# Cosmic_Pi_Analogue_V2_4_OHL_logo.net
KiCad netlist of a schematic drawn in EAGLE
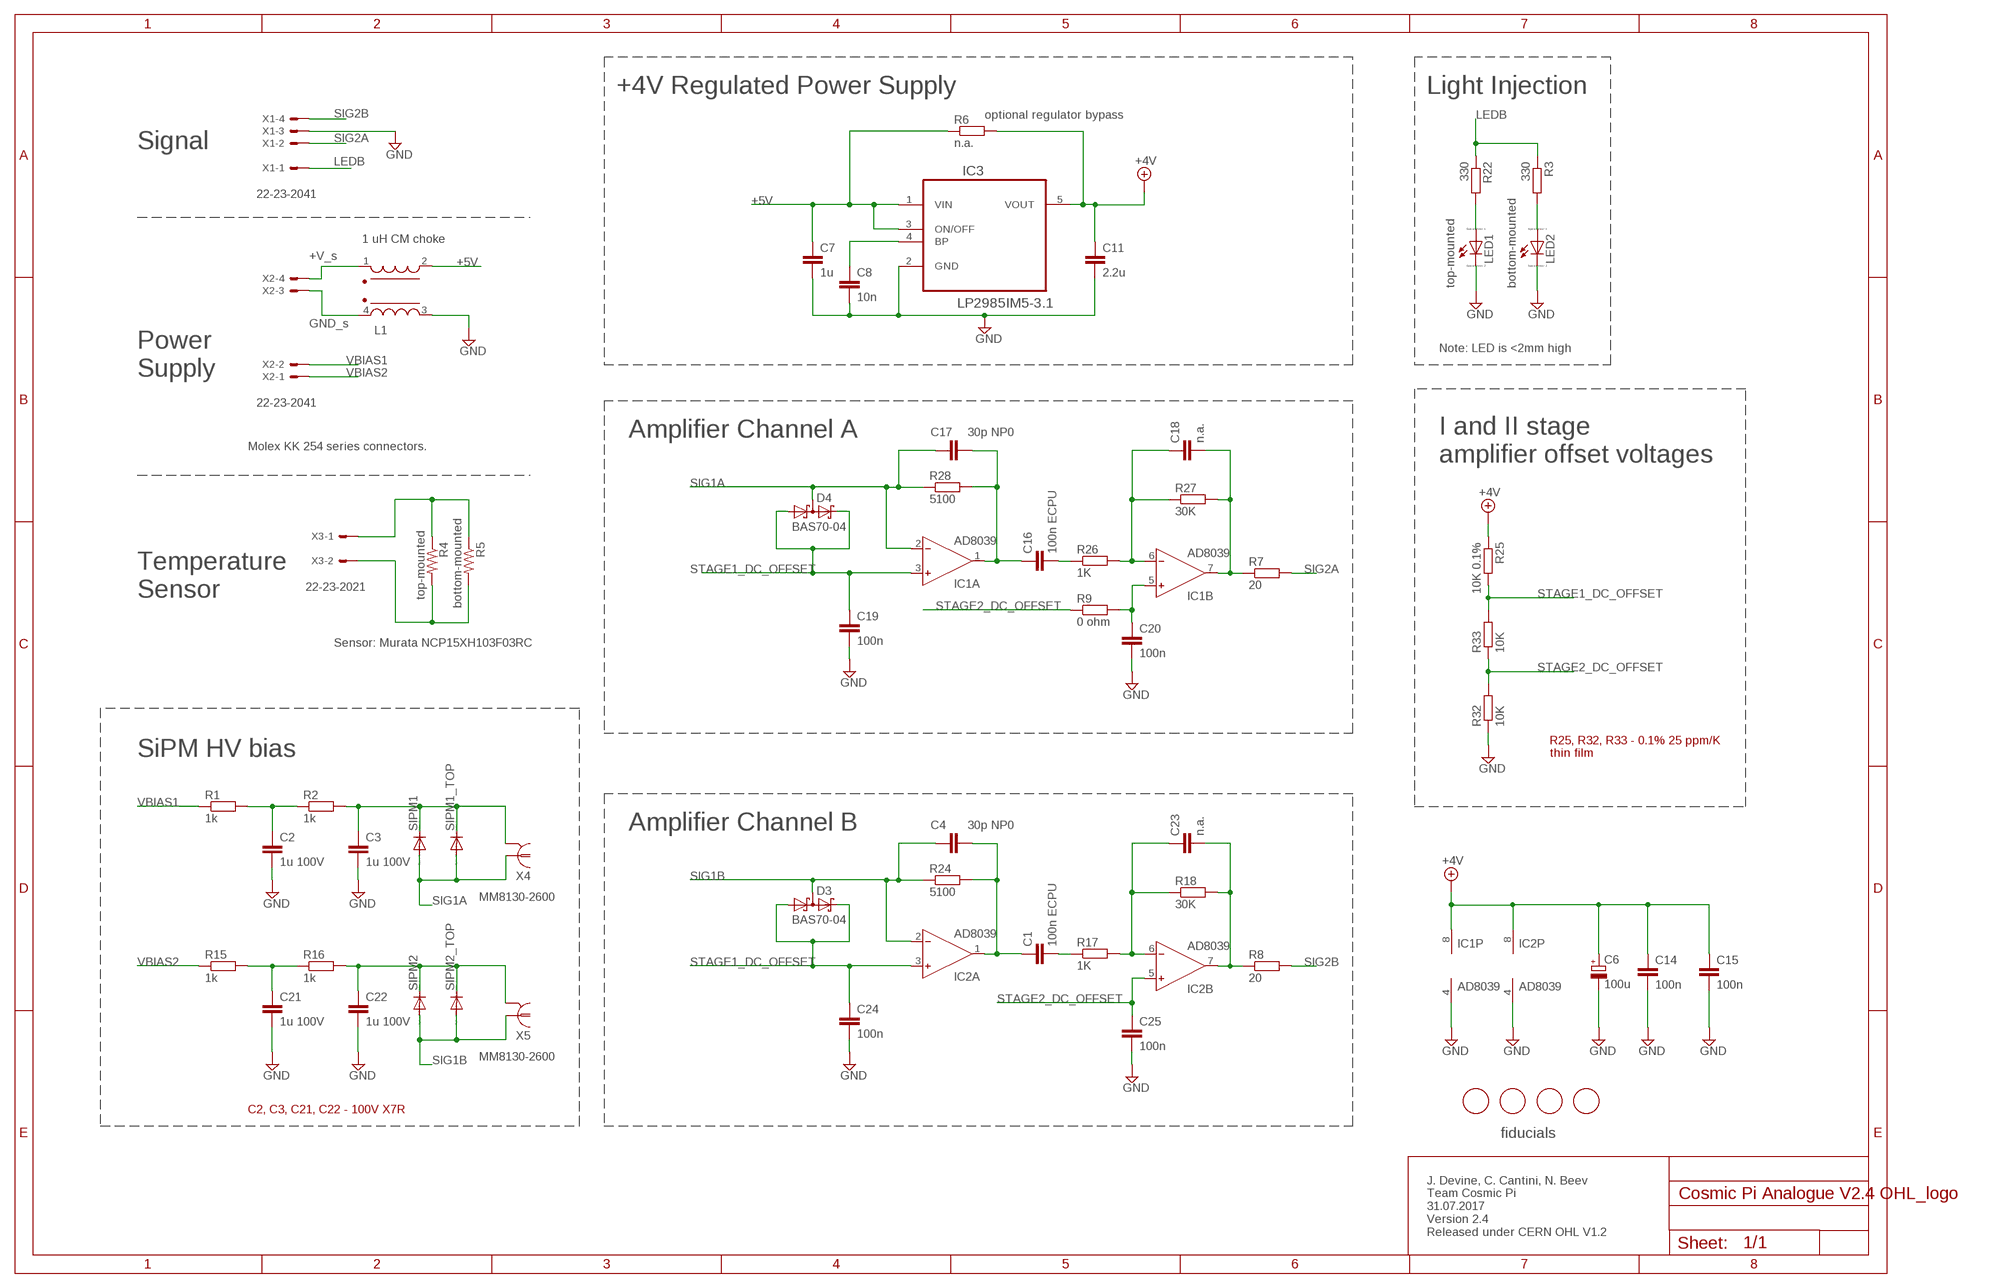
[diagram p0: schematic, sheet 1]

(export (version "E")
  (design (tool "Eeschema 10.0.6"))
  (components
    (comp (ref "C1")
      (value "100n ECPU")
      (footprint "eagle-import:C0805")
      (libsource (lib "eagle-import") (part "C-EUC0805"))
    )
    (comp (ref "C2")
      (value "1u 100V")
      (footprint "eagle-import:C1206")
      (libsource (lib "eagle-import") (part "C-EUC1206"))
    )
    (comp (ref "C3")
      (value "1u 100V")
      (footprint "eagle-import:C1206")
      (libsource (lib "eagle-import") (part "C-EUC1206"))
    )
    (comp (ref "C4")
      (value "30p NP0")
      (footprint "eagle-import:C0603")
      (libsource (lib "eagle-import") (part "C-EUC0603"))
    )
    (comp (ref "C6")
      (value "100u")
      (footprint "eagle-import:C_6032-28R")
      (libsource (lib "eagle-import") (part "CPOL-EUC/6032-28R"))
    )
    (comp (ref "C7")
      (value "1u")
      (footprint "eagle-import:C0603")
      (libsource (lib "eagle-import") (part "resistor_C-EUC0603"))
    )
    (comp (ref "C8")
      (value "10n")
      (footprint "eagle-import:C0603")
      (libsource (lib "eagle-import") (part "resistor_C-EUC0603"))
    )
    (comp (ref "C11")
      (value "2.2u")
      (footprint "eagle-import:C0603")
      (libsource (lib "eagle-import") (part "resistor_C-EUC0603"))
    )
    (comp (ref "C14")
      (value "100n")
      (footprint "eagle-import:C0603")
      (libsource (lib "eagle-import") (part "resistor_C-EUC0603"))
    )
    (comp (ref "C15")
      (value "100n")
      (footprint "eagle-import:C0603")
      (libsource (lib "eagle-import") (part "resistor_C-EUC0603"))
    )
    (comp (ref "C16")
      (value "100n ECPU")
      (footprint "eagle-import:C0805")
      (libsource (lib "eagle-import") (part "C-EUC0805"))
    )
    (comp (ref "C17")
      (value "30p NP0")
      (footprint "eagle-import:C0603")
      (libsource (lib "eagle-import") (part "C-EUC0603"))
    )
    (comp (ref "C18")
      (value "n.a.")
      (footprint "eagle-import:C0603")
      (libsource (lib "eagle-import") (part "C-EUC0603"))
    )
    (comp (ref "C19")
      (value "100n")
      (footprint "eagle-import:C0603")
      (libsource (lib "eagle-import") (part "resistor_C-EUC0603"))
    )
    (comp (ref "C20")
      (value "100n")
      (footprint "eagle-import:C0603")
      (libsource (lib "eagle-import") (part "resistor_C-EUC0603"))
    )
    (comp (ref "C21")
      (value "1u 100V")
      (footprint "eagle-import:C1206")
      (libsource (lib "eagle-import") (part "C-EUC1206"))
    )
    (comp (ref "C22")
      (value "1u 100V")
      (footprint "eagle-import:C1206")
      (libsource (lib "eagle-import") (part "C-EUC1206"))
    )
    (comp (ref "C23")
      (value "n.a.")
      (footprint "eagle-import:C0603")
      (libsource (lib "eagle-import") (part "C-EUC0603"))
    )
    (comp (ref "C24")
      (value "100n")
      (footprint "eagle-import:C0603")
      (libsource (lib "eagle-import") (part "resistor_C-EUC0603"))
    )
    (comp (ref "C25")
      (value "100n")
      (footprint "eagle-import:C0603")
      (libsource (lib "eagle-import") (part "resistor_C-EUC0603"))
    )
    (comp (ref "D3")
      (value "BAS70-04")
      (footprint "eagle-import:SOT23")
      (libsource (lib "eagle-import") (part "BAS70-04"))
    )
    (comp (ref "D4")
      (value "BAS70-04")
      (footprint "eagle-import:SOT23")
      (libsource (lib "eagle-import") (part "BAS70-04"))
    )
    (comp (ref "IC1")
      (value "AD8039")
      (footprint "eagle-import:SO8")
      (fields (field (name "MF") "ALTERA CORPORATION") (field (name "MPN") "AD8033ARZ"))
      (libsource (lib "eagle-import") (part "AD8033R"))
    )
    (comp (ref "IC2")
      (value "AD8039")
      (footprint "eagle-import:SO8")
      (fields (field (name "MF") "ALTERA CORPORATION") (field (name "MPN") "AD8033ARZ"))
      (libsource (lib "eagle-import") (part "AD8033R"))
    )
    (comp (ref "IC3")
      (value "LP2985IM5-3.1")
      (footprint "eagle-import:SOT95P284X120-5N")
      (libsource (lib "eagle-import") (part "LP2985IM5-3.1"))
    )
    (comp (ref "L1")
      (value "1 uH CM choke")
      (footprint "eagle-import:WE-CNSW_1812")
      (libsource (lib "eagle-import") (part "WE-CNSW_1812_744235601"))
    )
    (comp (ref "LED1")
      (value "top-mounted")
      (footprint "eagle-import:LED_SML0603")
      (libsource (lib "eagle-import") (part "LED_ESML0603"))
    )
    (comp (ref "LED2")
      (value "bottom-mounted")
      (footprint "eagle-import:LED_SML0603")
      (libsource (lib "eagle-import") (part "LED_ESML0603"))
    )
    (comp (ref "R1")
      (value "1k")
      (footprint "eagle-import:R1206")
      (libsource (lib "eagle-import") (part "R-EU_R1206"))
    )
    (comp (ref "R2")
      (value "1k")
      (footprint "eagle-import:R1206")
      (libsource (lib "eagle-import") (part "R-EU_R1206"))
    )
    (comp (ref "R3")
      (value "330")
      (footprint "eagle-import:R0603")
      (libsource (lib "eagle-import") (part "resistor_R-EU_R0603"))
    )
    (comp (ref "R4")
      (value "top-mounted")
      (footprint "eagle-import:R0402")
      (libsource (lib "eagle-import") (part "R-US_R0402"))
    )
    (comp (ref "R5")
      (value "bottom-mounted")
      (footprint "eagle-import:R0402")
      (libsource (lib "eagle-import") (part "R-US_R0402"))
    )
    (comp (ref "R6")
      (value "n.a.")
      (footprint "eagle-import:R0603")
      (libsource (lib "eagle-import") (part "R-EU_R0603"))
    )
    (comp (ref "R7")
      (value "20")
      (footprint "eagle-import:R0603")
      (libsource (lib "eagle-import") (part "R-EU_R0603"))
    )
    (comp (ref "R8")
      (value "20")
      (footprint "eagle-import:R0603")
      (libsource (lib "eagle-import") (part "R-EU_R0603"))
    )
    (comp (ref "R9")
      (value "0 ohm")
      (footprint "eagle-import:R1206")
      (libsource (lib "eagle-import") (part "R-EU_R1206"))
    )
    (comp (ref "R15")
      (value "1k")
      (footprint "eagle-import:R1206")
      (libsource (lib "eagle-import") (part "R-EU_R1206"))
    )
    (comp (ref "R16")
      (value "1k")
      (footprint "eagle-import:R1206")
      (libsource (lib "eagle-import") (part "R-EU_R1206"))
    )
    (comp (ref "R17")
      (value "1K")
      (footprint "eagle-import:R0603")
      (libsource (lib "eagle-import") (part "R-EU_R0603"))
    )
    (comp (ref "R18")
      (value "30K")
      (footprint "eagle-import:R0603")
      (libsource (lib "eagle-import") (part "R-EU_R0603"))
    )
    (comp (ref "R22")
      (value "330")
      (footprint "eagle-import:R0603")
      (libsource (lib "eagle-import") (part "resistor_R-EU_R0603"))
    )
    (comp (ref "R24")
      (value "5100")
      (footprint "eagle-import:R0603")
      (libsource (lib "eagle-import") (part "R-EU_R0603"))
    )
    (comp (ref "R25")
      (value "10K 0.1%")
      (footprint "eagle-import:R0805")
      (libsource (lib "eagle-import") (part "R-EU_R0805"))
    )
    (comp (ref "R26")
      (value "1K")
      (footprint "eagle-import:R0603")
      (libsource (lib "eagle-import") (part "R-EU_R0603"))
    )
    (comp (ref "R27")
      (value "30K")
      (footprint "eagle-import:R0603")
      (libsource (lib "eagle-import") (part "R-EU_R0603"))
    )
    (comp (ref "R28")
      (value "5100")
      (footprint "eagle-import:R0603")
      (libsource (lib "eagle-import") (part "R-EU_R0603"))
    )
    (comp (ref "R32")
      (value "10K")
      (footprint "eagle-import:R0805")
      (libsource (lib "eagle-import") (part "R-EU_R0805"))
    )
    (comp (ref "R33")
      (value "10K")
      (footprint "eagle-import:R0805")
      (libsource (lib "eagle-import") (part "R-EU_R0805"))
    )
    (comp (ref "SIPM1")
      (value "DIODE-ADVANSID")
      (footprint "eagle-import:ASD-NUV3S-P")
      (libsource (lib "eagle-import") (part "DIODE-ADVANSID"))
    )
    (comp (ref "SIPM1_TOP")
      (value "DIODE-ADVANSID")
      (footprint "eagle-import:ASD-NUV3S-P")
      (libsource (lib "eagle-import") (part "DIODE-ADVANSID"))
    )
    (comp (ref "SIPM2")
      (value "DIODE-ADVANSID")
      (footprint "eagle-import:ASD-NUV3S-P")
      (libsource (lib "eagle-import") (part "DIODE-ADVANSID"))
    )
    (comp (ref "SIPM2_TOP")
      (value "DIODE-ADVANSID")
      (footprint "eagle-import:ASD-NUV3S-P")
      (libsource (lib "eagle-import") (part "DIODE-ADVANSID"))
    )
    (comp (ref "U$2")
      (value "FIDUCIAL")
      (footprint "eagle-import:FIDUCIAL_1MM")
      (libsource (lib "eagle-import") (part "FIDUCIAL"))
    )
    (comp (ref "U$3")
      (value "FIDUCIAL")
      (footprint "eagle-import:FIDUCIAL_1MM")
      (libsource (lib "eagle-import") (part "FIDUCIAL"))
    )
    (comp (ref "U$4")
      (value "FIDUCIAL")
      (footprint "eagle-import:FIDUCIAL_1MM")
      (libsource (lib "eagle-import") (part "FIDUCIAL"))
    )
    (comp (ref "U$5")
      (value "FIDUCIAL")
      (footprint "eagle-import:FIDUCIAL_1MM")
      (libsource (lib "eagle-import") (part "FIDUCIAL"))
    )
    (comp (ref "X1")
      (value "22-23-2041")
      (footprint "eagle-import:22-23-2041")
      (fields (field (name "MF") "MOLEX"))
      (libsource (lib "eagle-import") (part "22-23-2041"))
    )
    (comp (ref "X2")
      (value "22-23-2041")
      (footprint "eagle-import:22-23-2041")
      (fields (field (name "MF") "MOLEX"))
      (libsource (lib "eagle-import") (part "22-23-2041"))
    )
    (comp (ref "X3")
      (value "22-23-2021")
      (footprint "eagle-import:22-23-2021")
      (fields (field (name "MF") "MOLEX"))
      (libsource (lib "eagle-import") (part "22-23-2021"))
    )
    (comp (ref "X4")
      (value "MM8130-2600")
      (footprint "eagle-import:MM8130-2600")
      (libsource (lib "eagle-import") (part "MM8130-2600"))
    )
    (comp (ref "X5")
      (value "MM8130-2600")
      (footprint "eagle-import:MM8130-2600")
      (libsource (lib "eagle-import") (part "MM8130-2600"))
    )
  )
  (nets
    (net (code "1") (name "+4V") (class "Default")
      (node (ref "C11") (pin "1") (pinfunction "1_1") (pintype "passive"))
      (node (ref "C14") (pin "1") (pinfunction "1_1") (pintype "passive"))
      (node (ref "C15") (pin "1") (pinfunction "1_1") (pintype "passive"))
      (node (ref "C6") (pin "+") (pinfunction "+_+") (pintype "passive"))
      (node (ref "IC1") (pin "8") (pinfunction "V+_8") (pintype "power_in"))
      (node (ref "IC2") (pin "8") (pinfunction "V+_8") (pintype "power_in"))
      (node (ref "IC3") (pin "5") (pinfunction "VOUT_5") (pintype "output"))
      (node (ref "R25") (pin "1") (pinfunction "1_1") (pintype "passive"))
      (node (ref "R6") (pin "2") (pinfunction "2_2") (pintype "passive"))
    )
    (net (code "2") (name "/+5V") (class "Default")
      (node (ref "C7") (pin "1") (pinfunction "1_1") (pintype "passive"))
      (node (ref "IC3") (pin "1") (pinfunction "VIN_1") (pintype "power_in"))
      (node (ref "IC3") (pin "3") (pinfunction "ON/OFF_3") (pintype "input"))
      (node (ref "L1") (pin "2") (pinfunction "3_2") (pintype "passive"))
      (node (ref "R6") (pin "1") (pinfunction "1_1") (pintype "passive"))
    )
    (net (code "3") (name "/LEDB") (class "Default")
      (node (ref "R22") (pin "1") (pinfunction "1_1") (pintype "passive"))
      (node (ref "R3") (pin "1") (pinfunction "1_1") (pintype "passive"))
      (node (ref "X1") (pin "1") (pinfunction "S_1") (pintype "passive"))
    )
    (net (code "4") (name "/SIG1A") (class "Default")
      (node (ref "C17") (pin "1") (pinfunction "1_1") (pintype "passive"))
      (node (ref "D4") (pin "3") (pinfunction "C1A2_3") (pintype "passive"))
      (node (ref "IC1") (pin "2") (pinfunction "IN-_2") (pintype "input"))
      (node (ref "R28") (pin "1") (pinfunction "1_1") (pintype "passive"))
      (node (ref "SIPM1") (pin "P$2") (pinfunction "A_P$2") (pintype "passive"))
      (node (ref "SIPM1_TOP") (pin "P$2") (pinfunction "A_P$2") (pintype "passive"))
      (node (ref "X4") (pin "P$1") (pinfunction "1_P$1") (pintype "passive"))
      (node (ref "X4") (pin "P$2") (pinfunction "1_P$2") (pintype "passive"))
    )
    (net (code "5") (name "/SIG1B") (class "Default")
      (node (ref "C4") (pin "1") (pinfunction "1_1") (pintype "passive"))
      (node (ref "D3") (pin "3") (pinfunction "C1A2_3") (pintype "passive"))
      (node (ref "IC2") (pin "2") (pinfunction "IN-_2") (pintype "input"))
      (node (ref "R24") (pin "1") (pinfunction "1_1") (pintype "passive"))
      (node (ref "SIPM2") (pin "P$2") (pinfunction "A_P$2") (pintype "passive"))
      (node (ref "SIPM2_TOP") (pin "P$2") (pinfunction "A_P$2") (pintype "passive"))
      (node (ref "X5") (pin "P$1") (pinfunction "1_P$1") (pintype "passive"))
      (node (ref "X5") (pin "P$2") (pinfunction "1_P$2") (pintype "passive"))
    )
    (net (code "6") (name "/SIG2A") (class "Default")
      (node (ref "R7") (pin "2") (pinfunction "2_2") (pintype "passive"))
      (node (ref "X1") (pin "2") (pinfunction "S_2") (pintype "passive"))
    )
    (net (code "7") (name "/SIG2B") (class "Default")
      (node (ref "R8") (pin "2") (pinfunction "2_2") (pintype "passive"))
      (node (ref "X1") (pin "4") (pinfunction "S_4") (pintype "passive"))
    )
    (net (code "8") (name "/STAGE1_DC_OFFSET") (class "Default")
      (node (ref "C19") (pin "1") (pinfunction "1_1") (pintype "passive"))
      (node (ref "C24") (pin "1") (pinfunction "1_1") (pintype "passive"))
      (node (ref "D3") (pin "1") (pinfunction "A1_1") (pintype "passive"))
      (node (ref "D3") (pin "2") (pinfunction "C2_2") (pintype "passive"))
      (node (ref "D4") (pin "1") (pinfunction "A1_1") (pintype "passive"))
      (node (ref "D4") (pin "2") (pinfunction "C2_2") (pintype "passive"))
      (node (ref "IC1") (pin "3") (pinfunction "IN+_3") (pintype "input"))
      (node (ref "IC2") (pin "3") (pinfunction "IN+_3") (pintype "input"))
      (node (ref "R25") (pin "2") (pinfunction "2_2") (pintype "passive"))
      (node (ref "R33") (pin "2") (pinfunction "2_2") (pintype "passive"))
    )
    (net (code "9") (name "/STAGE2_DC_OFFSET") (class "Default")
      (node (ref "C25") (pin "1") (pinfunction "1_1") (pintype "passive"))
      (node (ref "IC2") (pin "5") (pinfunction "IN+_5") (pintype "input"))
      (node (ref "R32") (pin "2") (pinfunction "2_2") (pintype "passive"))
      (node (ref "R33") (pin "1") (pinfunction "1_1") (pintype "passive"))
      (node (ref "R9") (pin "1") (pinfunction "1_1") (pintype "passive"))
    )
    (net (code "10") (name "/VBIAS1") (class "Default")
      (node (ref "R1") (pin "1") (pinfunction "1_1") (pintype "passive"))
      (node (ref "X2") (pin "2") (pinfunction "S_2") (pintype "passive"))
    )
    (net (code "11") (name "/VBIAS2") (class "Default")
      (node (ref "R15") (pin "1") (pinfunction "1_1") (pintype "passive"))
      (node (ref "X2") (pin "1") (pinfunction "S_1") (pintype "passive"))
    )
    (net (code "12") (name "GND") (class "Default")
      (node (ref "C11") (pin "2") (pinfunction "2_2") (pintype "passive"))
      (node (ref "C14") (pin "2") (pinfunction "2_2") (pintype "passive"))
      (node (ref "C15") (pin "2") (pinfunction "2_2") (pintype "passive"))
      (node (ref "C19") (pin "2") (pinfunction "2_2") (pintype "passive"))
      (node (ref "C2") (pin "2") (pinfunction "2_2") (pintype "passive"))
      (node (ref "C20") (pin "2") (pinfunction "2_2") (pintype "passive"))
      (node (ref "C21") (pin "2") (pinfunction "2_2") (pintype "passive"))
      (node (ref "C22") (pin "2") (pinfunction "2_2") (pintype "passive"))
      (node (ref "C24") (pin "2") (pinfunction "2_2") (pintype "passive"))
      (node (ref "C25") (pin "2") (pinfunction "2_2") (pintype "passive"))
      (node (ref "C3") (pin "2") (pinfunction "2_2") (pintype "passive"))
      (node (ref "C6") (pin "-") (pinfunction "-_-") (pintype "passive"))
      (node (ref "C7") (pin "2") (pinfunction "2_2") (pintype "passive"))
      (node (ref "C8") (pin "2") (pinfunction "2_2") (pintype "passive"))
      (node (ref "IC1") (pin "4") (pinfunction "V-_4") (pintype "power_in"))
      (node (ref "IC2") (pin "4") (pinfunction "V-_4") (pintype "power_in"))
      (node (ref "IC3") (pin "2") (pinfunction "GND_2") (pintype "passive"))
      (node (ref "L1") (pin "3") (pinfunction "2_3") (pintype "passive"))
      (node (ref "LED1") (pin "C") (pinfunction "C_C") (pintype "passive"))
      (node (ref "LED2") (pin "C") (pinfunction "C_C") (pintype "passive"))
      (node (ref "R32") (pin "1") (pinfunction "1_1") (pintype "passive"))
      (node (ref "X1") (pin "3") (pinfunction "S_3") (pintype "passive"))
    )
    (net (code "13") (name "Net-(C1-Pad2)") (class "Default")
      (node (ref "C1") (pin "2") (pinfunction "2_2") (pintype "passive"))
      (node (ref "R17") (pin "1") (pinfunction "1_1") (pintype "passive"))
    )
    (net (code "14") (name "Net-(C2-Pad1)") (class "Default")
      (node (ref "C2") (pin "1") (pinfunction "1_1") (pintype "passive"))
      (node (ref "R1") (pin "2") (pinfunction "2_2") (pintype "passive"))
      (node (ref "R2") (pin "1") (pinfunction "1_1") (pintype "passive"))
    )
    (net (code "15") (name "Net-(C16-Pad2)") (class "Default")
      (node (ref "C16") (pin "2") (pinfunction "2_2") (pintype "passive"))
      (node (ref "R26") (pin "1") (pinfunction "1_1") (pintype "passive"))
    )
    (net (code "16") (name "Net-(C21-Pad1)") (class "Default")
      (node (ref "C21") (pin "1") (pinfunction "1_1") (pintype "passive"))
      (node (ref "R15") (pin "2") (pinfunction "2_2") (pintype "passive"))
      (node (ref "R16") (pin "1") (pinfunction "1_1") (pintype "passive"))
    )
    (net (code "17") (name "Net-(IC1A-OUT)") (class "Default")
      (node (ref "C16") (pin "1") (pinfunction "1_1") (pintype "passive"))
      (node (ref "C17") (pin "2") (pinfunction "2_2") (pintype "passive"))
      (node (ref "IC1") (pin "1") (pinfunction "OUT_1") (pintype "output"))
      (node (ref "R28") (pin "2") (pinfunction "2_2") (pintype "passive"))
    )
    (net (code "18") (name "Net-(IC1B-IN+)") (class "Default")
      (node (ref "C20") (pin "1") (pinfunction "1_1") (pintype "passive"))
      (node (ref "IC1") (pin "5") (pinfunction "IN+_5") (pintype "input"))
      (node (ref "R9") (pin "2") (pinfunction "2_2") (pintype "passive"))
    )
    (net (code "19") (name "Net-(IC1B-IN-)") (class "Default")
      (node (ref "C18") (pin "1") (pinfunction "1_1") (pintype "passive"))
      (node (ref "IC1") (pin "6") (pinfunction "IN-_6") (pintype "input"))
      (node (ref "R26") (pin "2") (pinfunction "2_2") (pintype "passive"))
      (node (ref "R27") (pin "1") (pinfunction "1_1") (pintype "passive"))
    )
    (net (code "20") (name "Net-(IC1B-OUT)") (class "Default")
      (node (ref "C18") (pin "2") (pinfunction "2_2") (pintype "passive"))
      (node (ref "IC1") (pin "7") (pinfunction "OUT_7") (pintype "output"))
      (node (ref "R27") (pin "2") (pinfunction "2_2") (pintype "passive"))
      (node (ref "R7") (pin "1") (pinfunction "1_1") (pintype "passive"))
    )
    (net (code "21") (name "Net-(IC2A-OUT)") (class "Default")
      (node (ref "C1") (pin "1") (pinfunction "1_1") (pintype "passive"))
      (node (ref "C4") (pin "2") (pinfunction "2_2") (pintype "passive"))
      (node (ref "IC2") (pin "1") (pinfunction "OUT_1") (pintype "output"))
      (node (ref "R24") (pin "2") (pinfunction "2_2") (pintype "passive"))
    )
    (net (code "22") (name "Net-(IC2B-IN-)") (class "Default")
      (node (ref "C23") (pin "1") (pinfunction "1_1") (pintype "passive"))
      (node (ref "IC2") (pin "6") (pinfunction "IN-_6") (pintype "input"))
      (node (ref "R17") (pin "2") (pinfunction "2_2") (pintype "passive"))
      (node (ref "R18") (pin "1") (pinfunction "1_1") (pintype "passive"))
    )
    (net (code "23") (name "Net-(IC2B-OUT)") (class "Default")
      (node (ref "C23") (pin "2") (pinfunction "2_2") (pintype "passive"))
      (node (ref "IC2") (pin "7") (pinfunction "OUT_7") (pintype "output"))
      (node (ref "R18") (pin "2") (pinfunction "2_2") (pintype "passive"))
      (node (ref "R8") (pin "1") (pinfunction "1_1") (pintype "passive"))
    )
    (net (code "24") (name "Net-(IC3-BP)") (class "Default")
      (node (ref "C8") (pin "1") (pinfunction "1_1") (pintype "passive"))
      (node (ref "IC3") (pin "4") (pinfunction "BP_4") (pintype "input"))
    )
    (net (code "25") (name "Net-(L1-1)") (class "Default")
      (node (ref "L1") (pin "4") (pinfunction "1_4") (pintype "passive"))
      (node (ref "X2") (pin "3") (pinfunction "S_3") (pintype "passive"))
    )
    (net (code "26") (name "Net-(L1-4)") (class "Default")
      (node (ref "L1") (pin "1") (pinfunction "4_1") (pintype "passive"))
      (node (ref "X2") (pin "4") (pinfunction "S_4") (pintype "passive"))
    )
    (net (code "27") (name "Net-(LED1-PadA)") (class "Default")
      (node (ref "LED1") (pin "A") (pinfunction "A_A") (pintype "passive"))
      (node (ref "R22") (pin "2") (pinfunction "2_2") (pintype "passive"))
    )
    (net (code "28") (name "Net-(LED2-PadA)") (class "Default")
      (node (ref "LED2") (pin "A") (pinfunction "A_A") (pintype "passive"))
      (node (ref "R3") (pin "2") (pinfunction "2_2") (pintype "passive"))
    )
    (net (code "29") (name "Net-(SIPM1-C)") (class "Default")
      (node (ref "C3") (pin "1") (pinfunction "1_1") (pintype "passive"))
      (node (ref "R2") (pin "2") (pinfunction "2_2") (pintype "passive"))
      (node (ref "SIPM1") (pin "P$1") (pinfunction "C_P$1") (pintype "passive"))
      (node (ref "SIPM1_TOP") (pin "P$1") (pinfunction "C_P$1") (pintype "passive"))
      (node (ref "X4") (pin "P$3") (pinfunction "2_P$3") (pintype "passive"))
      (node (ref "X4") (pin "P$4") (pinfunction "2_P$4") (pintype "passive"))
      (node (ref "X4") (pin "P$5") (pinfunction "2_P$5") (pintype "passive"))
      (node (ref "X4") (pin "P$6") (pinfunction "2_P$6") (pintype "passive"))
    )
    (net (code "30") (name "Net-(SIPM2-C)") (class "Default")
      (node (ref "C22") (pin "1") (pinfunction "1_1") (pintype "passive"))
      (node (ref "R16") (pin "2") (pinfunction "2_2") (pintype "passive"))
      (node (ref "SIPM2") (pin "P$1") (pinfunction "C_P$1") (pintype "passive"))
      (node (ref "SIPM2_TOP") (pin "P$1") (pinfunction "C_P$1") (pintype "passive"))
      (node (ref "X5") (pin "P$3") (pinfunction "2_P$3") (pintype "passive"))
      (node (ref "X5") (pin "P$4") (pinfunction "2_P$4") (pintype "passive"))
      (node (ref "X5") (pin "P$5") (pinfunction "2_P$5") (pintype "passive"))
      (node (ref "X5") (pin "P$6") (pinfunction "2_P$6") (pintype "passive"))
    )
    (net (code "31") (name "Net-(X3A-S)") (class "Default")
      (node (ref "R4") (pin "1") (pinfunction "1_1") (pintype "passive"))
      (node (ref "R5") (pin "1") (pinfunction "1_1") (pintype "passive"))
      (node (ref "X3") (pin "1") (pinfunction "S_1") (pintype "passive"))
    )
    (net (code "32") (name "Net-(X3B-S)") (class "Default")
      (node (ref "R4") (pin "2") (pinfunction "2_2") (pintype "passive"))
      (node (ref "R5") (pin "2") (pinfunction "2_2") (pintype "passive"))
      (node (ref "X3") (pin "2") (pinfunction "S_2") (pintype "passive"))
    )
  )
)
